# main.net
KiCad netlist of a schematic drawn in Altium Designer
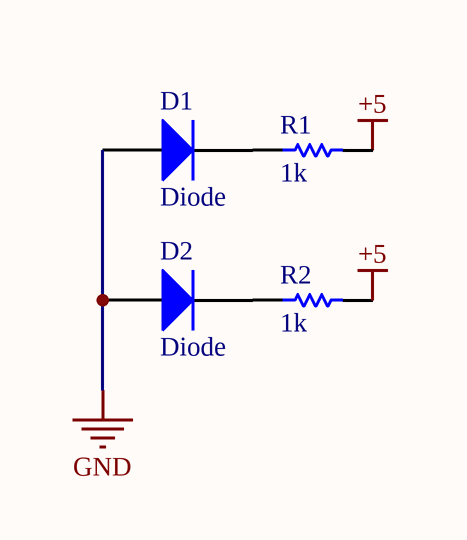
[diagram p0: main.SchDoc]

(export (version "E")
  (design (tool "Eeschema 10.0.6"))
  (components
    (comp (ref "D1")
      (value "Diode")
      (footprint "LED3mm")
      (description "Default Diode")
      (fields (field (name "PUBLISHER") "Altium Limited"))
      (libsource (lib "Miscellaneous Devices") (part "Diode"))
    )
    (comp (ref "D2")
      (value "Diode")
      (footprint "LED3mm")
      (description "Default Diode")
      (fields (field (name "PUBLISHER") "Altium Limited"))
      (libsource (lib "Miscellaneous Devices") (part "Diode"))
    )
    (comp (ref "R1")
      (value "1k")
      (footprint "RR_0603")
      (description "Resistor")
      (libsource (lib "Miscellaneous Devices") (part "Res1"))
    )
    (comp (ref "R2")
      (value "1k")
      (footprint "RR_0603")
      (description "Resistor")
      (libsource (lib "Miscellaneous Devices") (part "Res1"))
    )
  )
  (nets
    (net (code "1") (name "+5") (class "Default")
      (node (ref "R1") (pin "2") (pinfunction "2_2") (pintype "passive"))
      (node (ref "R2") (pin "2") (pinfunction "2_2") (pintype "passive"))
    )
    (net (code "2") (name "GND") (class "Default")
      (node (ref "D1") (pin "1") (pinfunction "A_1") (pintype "passive"))
      (node (ref "D2") (pin "1") (pinfunction "A_1") (pintype "passive"))
    )
    (net (code "3") (name "Net-(D1-K)") (class "Default")
      (node (ref "D1") (pin "2") (pinfunction "K_2") (pintype "passive"))
      (node (ref "R1") (pin "1") (pinfunction "1_1") (pintype "passive"))
    )
    (net (code "4") (name "Net-(D2-K)") (class "Default")
      (node (ref "D2") (pin "2") (pinfunction "K_2") (pintype "passive"))
      (node (ref "R2") (pin "1") (pinfunction "1_1") (pintype "passive"))
    )
  )
)
